# microcontroller.net
KiCad netlist of a schematic drawn in Altium Designer
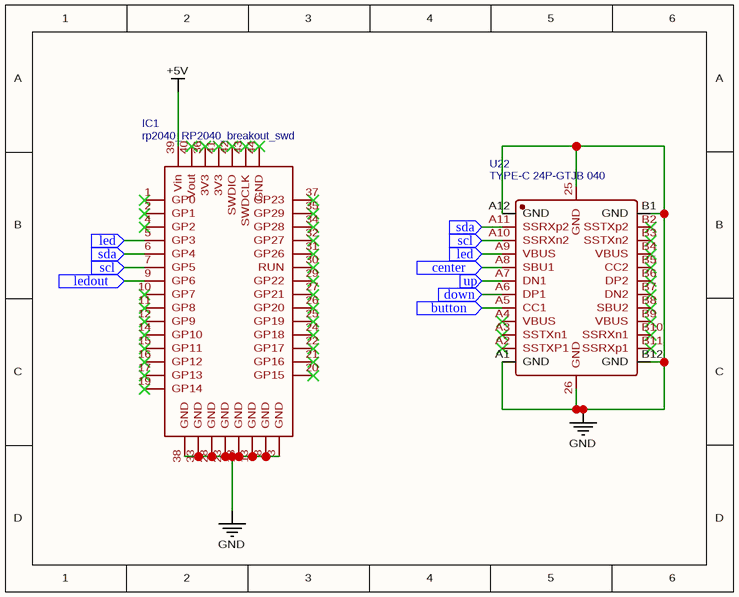
[diagram p0: microcontroller.schdoc]

(export (version "E")
  (design (tool "Eeschema 10.0.6"))
  (components
    (comp (ref "IC1")
      (value "rp2040_RP2040_breakout_swd")
      (fields (field (name "CONTRIBUTOR") "rataweb"))
      (libsource (lib "altium-import") (part "root_0_rp2040_RP2040_breakout_swd_"))
    )
    (comp (ref "U22")
      (value "TYPE-C 24P-GTJB 040")
      (fields (field (name "MANUFACTURER") "SHOU HAN(首韩)") (field (name "CONTRIBUTOR") "lcsc"))
      (libsource (lib "altium-import") (part "root_0_TYPE-C 24P-GTJB 040_"))
    )
  )
  (nets
    (net (code "1") (name "+5V") (class "Default")
      (node (ref "IC1") (pin "39") (pinfunction "Vin_39") (pintype "passive"))
    )
    (net (code "2") (name "/button") (class "Default")
      (node (ref "U22") (pin "A5") (pinfunction "CC1_A5") (pintype "passive"))
    )
    (net (code "3") (name "/center") (class "Default")
      (node (ref "U22") (pin "A8") (pinfunction "SBU1_A8") (pintype "passive"))
    )
    (net (code "4") (name "/down") (class "Default")
      (node (ref "U22") (pin "A6") (pinfunction "DP1_A6") (pintype "passive"))
    )
    (net (code "5") (name "/led") (class "Default")
      (node (ref "IC1") (pin "5") (pinfunction "GP3_5") (pintype "passive"))
      (node (ref "U22") (pin "A9") (pinfunction "VBUS_A9") (pintype "passive"))
    )
    (net (code "6") (name "/ledout") (class "Default")
      (node (ref "IC1") (pin "9") (pinfunction "GP6_9") (pintype "passive"))
    )
    (net (code "7") (name "/scl") (class "Default")
      (node (ref "IC1") (pin "7") (pinfunction "GP5_7") (pintype "passive"))
      (node (ref "U22") (pin "A10") (pinfunction "SSRXn2_A10") (pintype "passive"))
    )
    (net (code "8") (name "/sda") (class "Default")
      (node (ref "IC1") (pin "6") (pinfunction "GP4_6") (pintype "passive"))
      (node (ref "U22") (pin "A11") (pinfunction "SSRXp2_A11") (pintype "passive"))
    )
    (net (code "9") (name "/up") (class "Default")
      (node (ref "U22") (pin "A7") (pinfunction "DN1_A7") (pintype "passive"))
    )
    (net (code "10") (name "GND") (class "Default")
      (node (ref "IC1") (pin "13") (pinfunction "GND_13") (pintype "passive"))
      (node (ref "IC1") (pin "18") (pinfunction "GND_18") (pintype "passive"))
      (node (ref "IC1") (pin "23") (pinfunction "GND_23") (pintype "passive"))
      (node (ref "IC1") (pin "28") (pinfunction "GND_28") (pintype "passive"))
      (node (ref "IC1") (pin "3") (pinfunction "GND_3") (pintype "passive"))
      (node (ref "IC1") (pin "33") (pinfunction "GND_33") (pintype "passive"))
      (node (ref "IC1") (pin "38") (pinfunction "GND_38") (pintype "passive"))
      (node (ref "IC1") (pin "8") (pinfunction "GND_8") (pintype "passive"))
      (node (ref "U22") (pin "25") (pinfunction "GND_25") (pintype "passive"))
      (node (ref "U22") (pin "26") (pinfunction "GND_26") (pintype "passive"))
      (node (ref "U22") (pin "A1") (pinfunction "GND_A1") (pintype "passive"))
      (node (ref "U22") (pin "A12") (pinfunction "GND_A12") (pintype "passive"))
      (node (ref "U22") (pin "B1") (pinfunction "GND_B1") (pintype "passive"))
      (node (ref "U22") (pin "B12") (pinfunction "GND_B12") (pintype "passive"))
    )
    (net (code "11") (name "unconnected-(IC1-3V3-Pad36)") (class "Default")
      (node (ref "IC1") (pin "36") (pinfunction "3V3_36") (pintype "passive+no_connect"))
    )
    (net (code "12") (name "unconnected-(IC1-3V3-Pad41)") (class "Default")
      (node (ref "IC1") (pin "41") (pinfunction "3V3_41") (pintype "passive+no_connect"))
    )
    (net (code "13") (name "unconnected-(IC1-GND-Pad44)") (class "Default")
      (node (ref "IC1") (pin "44") (pinfunction "GND_44") (pintype "passive+no_connect"))
    )
    (net (code "14") (name "unconnected-(IC1-GP0-Pad1)") (class "Default")
      (node (ref "IC1") (pin "1") (pinfunction "GP0_1") (pintype "passive+no_connect"))
    )
    (net (code "15") (name "unconnected-(IC1-GP1-Pad2)") (class "Default")
      (node (ref "IC1") (pin "2") (pinfunction "GP1_2") (pintype "passive+no_connect"))
    )
    (net (code "16") (name "unconnected-(IC1-GP2-Pad4)") (class "Default")
      (node (ref "IC1") (pin "4") (pinfunction "GP2_4") (pintype "passive+no_connect"))
    )
    (net (code "17") (name "unconnected-(IC1-GP7-Pad10)") (class "Default")
      (node (ref "IC1") (pin "10") (pinfunction "GP7_10") (pintype "passive+no_connect"))
    )
    (net (code "18") (name "unconnected-(IC1-GP8-Pad11)") (class "Default")
      (node (ref "IC1") (pin "11") (pinfunction "GP8_11") (pintype "passive+no_connect"))
    )
    (net (code "19") (name "unconnected-(IC1-GP9-Pad12)") (class "Default")
      (node (ref "IC1") (pin "12") (pinfunction "GP9_12") (pintype "passive+no_connect"))
    )
    (net (code "20") (name "unconnected-(IC1-GP10-Pad14)") (class "Default")
      (node (ref "IC1") (pin "14") (pinfunction "GP10_14") (pintype "passive+no_connect"))
    )
    (net (code "21") (name "unconnected-(IC1-GP11-Pad15)") (class "Default")
      (node (ref "IC1") (pin "15") (pinfunction "GP11_15") (pintype "passive+no_connect"))
    )
    (net (code "22") (name "unconnected-(IC1-GP12-Pad16)") (class "Default")
      (node (ref "IC1") (pin "16") (pinfunction "GP12_16") (pintype "passive+no_connect"))
    )
    (net (code "23") (name "unconnected-(IC1-GP13-Pad17)") (class "Default")
      (node (ref "IC1") (pin "17") (pinfunction "GP13_17") (pintype "passive+no_connect"))
    )
    (net (code "24") (name "unconnected-(IC1-GP14-Pad19)") (class "Default")
      (node (ref "IC1") (pin "19") (pinfunction "GP14_19") (pintype "passive+no_connect"))
    )
    (net (code "25") (name "unconnected-(IC1-GP15-Pad20)") (class "Default")
      (node (ref "IC1") (pin "20") (pinfunction "GP15_20") (pintype "passive+no_connect"))
    )
    (net (code "26") (name "unconnected-(IC1-GP16-Pad21)") (class "Default")
      (node (ref "IC1") (pin "21") (pinfunction "GP16_21") (pintype "passive+no_connect"))
    )
    (net (code "27") (name "unconnected-(IC1-GP17-Pad22)") (class "Default")
      (node (ref "IC1") (pin "22") (pinfunction "GP17_22") (pintype "passive+no_connect"))
    )
    (net (code "28") (name "unconnected-(IC1-GP18-Pad24)") (class "Default")
      (node (ref "IC1") (pin "24") (pinfunction "GP18_24") (pintype "passive+no_connect"))
    )
    (net (code "29") (name "unconnected-(IC1-GP19-Pad25)") (class "Default")
      (node (ref "IC1") (pin "25") (pinfunction "GP19_25") (pintype "passive+no_connect"))
    )
    (net (code "30") (name "unconnected-(IC1-GP20-Pad26)") (class "Default")
      (node (ref "IC1") (pin "26") (pinfunction "GP20_26") (pintype "passive+no_connect"))
    )
    (net (code "31") (name "unconnected-(IC1-GP21-Pad27)") (class "Default")
      (node (ref "IC1") (pin "27") (pinfunction "GP21_27") (pintype "passive+no_connect"))
    )
    (net (code "32") (name "unconnected-(IC1-GP22-Pad29)") (class "Default")
      (node (ref "IC1") (pin "29") (pinfunction "GP22_29") (pintype "passive+no_connect"))
    )
    (net (code "33") (name "unconnected-(IC1-GP23-Pad37)") (class "Default")
      (node (ref "IC1") (pin "37") (pinfunction "GP23_37") (pintype "passive+no_connect"))
    )
    (net (code "34") (name "unconnected-(IC1-GP26-Pad31)") (class "Default")
      (node (ref "IC1") (pin "31") (pinfunction "GP26_31") (pintype "passive+no_connect"))
    )
    (net (code "35") (name "unconnected-(IC1-GP27-Pad32)") (class "Default")
      (node (ref "IC1") (pin "32") (pinfunction "GP27_32") (pintype "passive+no_connect"))
    )
    (net (code "36") (name "unconnected-(IC1-GP28-Pad34)") (class "Default")
      (node (ref "IC1") (pin "34") (pinfunction "GP28_34") (pintype "passive+no_connect"))
    )
    (net (code "37") (name "unconnected-(IC1-GP29-Pad35)") (class "Default")
      (node (ref "IC1") (pin "35") (pinfunction "GP29_35") (pintype "passive+no_connect"))
    )
    (net (code "38") (name "unconnected-(IC1-RUN-Pad30)") (class "Default")
      (node (ref "IC1") (pin "30") (pinfunction "RUN_30") (pintype "passive+no_connect"))
    )
    (net (code "39") (name "unconnected-(IC1-SWDCLK-Pad43)") (class "Default")
      (node (ref "IC1") (pin "43") (pinfunction "SWDCLK_43") (pintype "passive+no_connect"))
    )
    (net (code "40") (name "unconnected-(IC1-SWDIO-Pad42)") (class "Default")
      (node (ref "IC1") (pin "42") (pinfunction "SWDIO_42") (pintype "passive+no_connect"))
    )
    (net (code "41") (name "unconnected-(IC1-Vout-Pad40)") (class "Default")
      (node (ref "IC1") (pin "40") (pinfunction "Vout_40") (pintype "passive+no_connect"))
    )
    (net (code "42") (name "unconnected-(U22-CC2-PadB5)") (class "Default")
      (node (ref "U22") (pin "B5") (pinfunction "CC2_B5") (pintype "passive+no_connect"))
    )
    (net (code "43") (name "unconnected-(U22-DN2-PadB7)") (class "Default")
      (node (ref "U22") (pin "B7") (pinfunction "DN2_B7") (pintype "passive+no_connect"))
    )
    (net (code "44") (name "unconnected-(U22-DP2-PadB6)") (class "Default")
      (node (ref "U22") (pin "B6") (pinfunction "DP2_B6") (pintype "passive+no_connect"))
    )
    (net (code "45") (name "unconnected-(U22-SBU2-PadB8)") (class "Default")
      (node (ref "U22") (pin "B8") (pinfunction "SBU2_B8") (pintype "passive+no_connect"))
    )
    (net (code "46") (name "unconnected-(U22-SSRXn1-PadB10)") (class "Default")
      (node (ref "U22") (pin "B10") (pinfunction "SSRXn1_B10") (pintype "passive+no_connect"))
    )
    (net (code "47") (name "unconnected-(U22-SSRXp1-PadB11)") (class "Default")
      (node (ref "U22") (pin "B11") (pinfunction "SSRXp1_B11") (pintype "passive+no_connect"))
    )
    (net (code "48") (name "unconnected-(U22-SSTXP1-PadA2)") (class "Default")
      (node (ref "U22") (pin "A2") (pinfunction "SSTXP1_A2") (pintype "passive+no_connect"))
    )
    (net (code "49") (name "unconnected-(U22-SSTXn1-PadA3)") (class "Default")
      (node (ref "U22") (pin "A3") (pinfunction "SSTXn1_A3") (pintype "passive+no_connect"))
    )
    (net (code "50") (name "unconnected-(U22-SSTXn2-PadB3)") (class "Default")
      (node (ref "U22") (pin "B3") (pinfunction "SSTXn2_B3") (pintype "passive+no_connect"))
    )
    (net (code "51") (name "unconnected-(U22-SSTXp2-PadB2)") (class "Default")
      (node (ref "U22") (pin "B2") (pinfunction "SSTXp2_B2") (pintype "passive+no_connect"))
    )
    (net (code "52") (name "unconnected-(U22-VBUS-PadA4)") (class "Default")
      (node (ref "U22") (pin "A4") (pinfunction "VBUS_A4") (pintype "passive+no_connect"))
    )
    (net (code "53") (name "unconnected-(U22-VBUS-PadB4)") (class "Default")
      (node (ref "U22") (pin "B4") (pinfunction "VBUS_B4") (pintype "passive+no_connect"))
    )
    (net (code "54") (name "unconnected-(U22-VBUS-PadB9)") (class "Default")
      (node (ref "U22") (pin "B9") (pinfunction "VBUS_B9") (pintype "passive+no_connect"))
    )
  )
)
